# openSX70_MEROE_V7-1_20190603.net
KiCad netlist of a schematic drawn in EAGLE
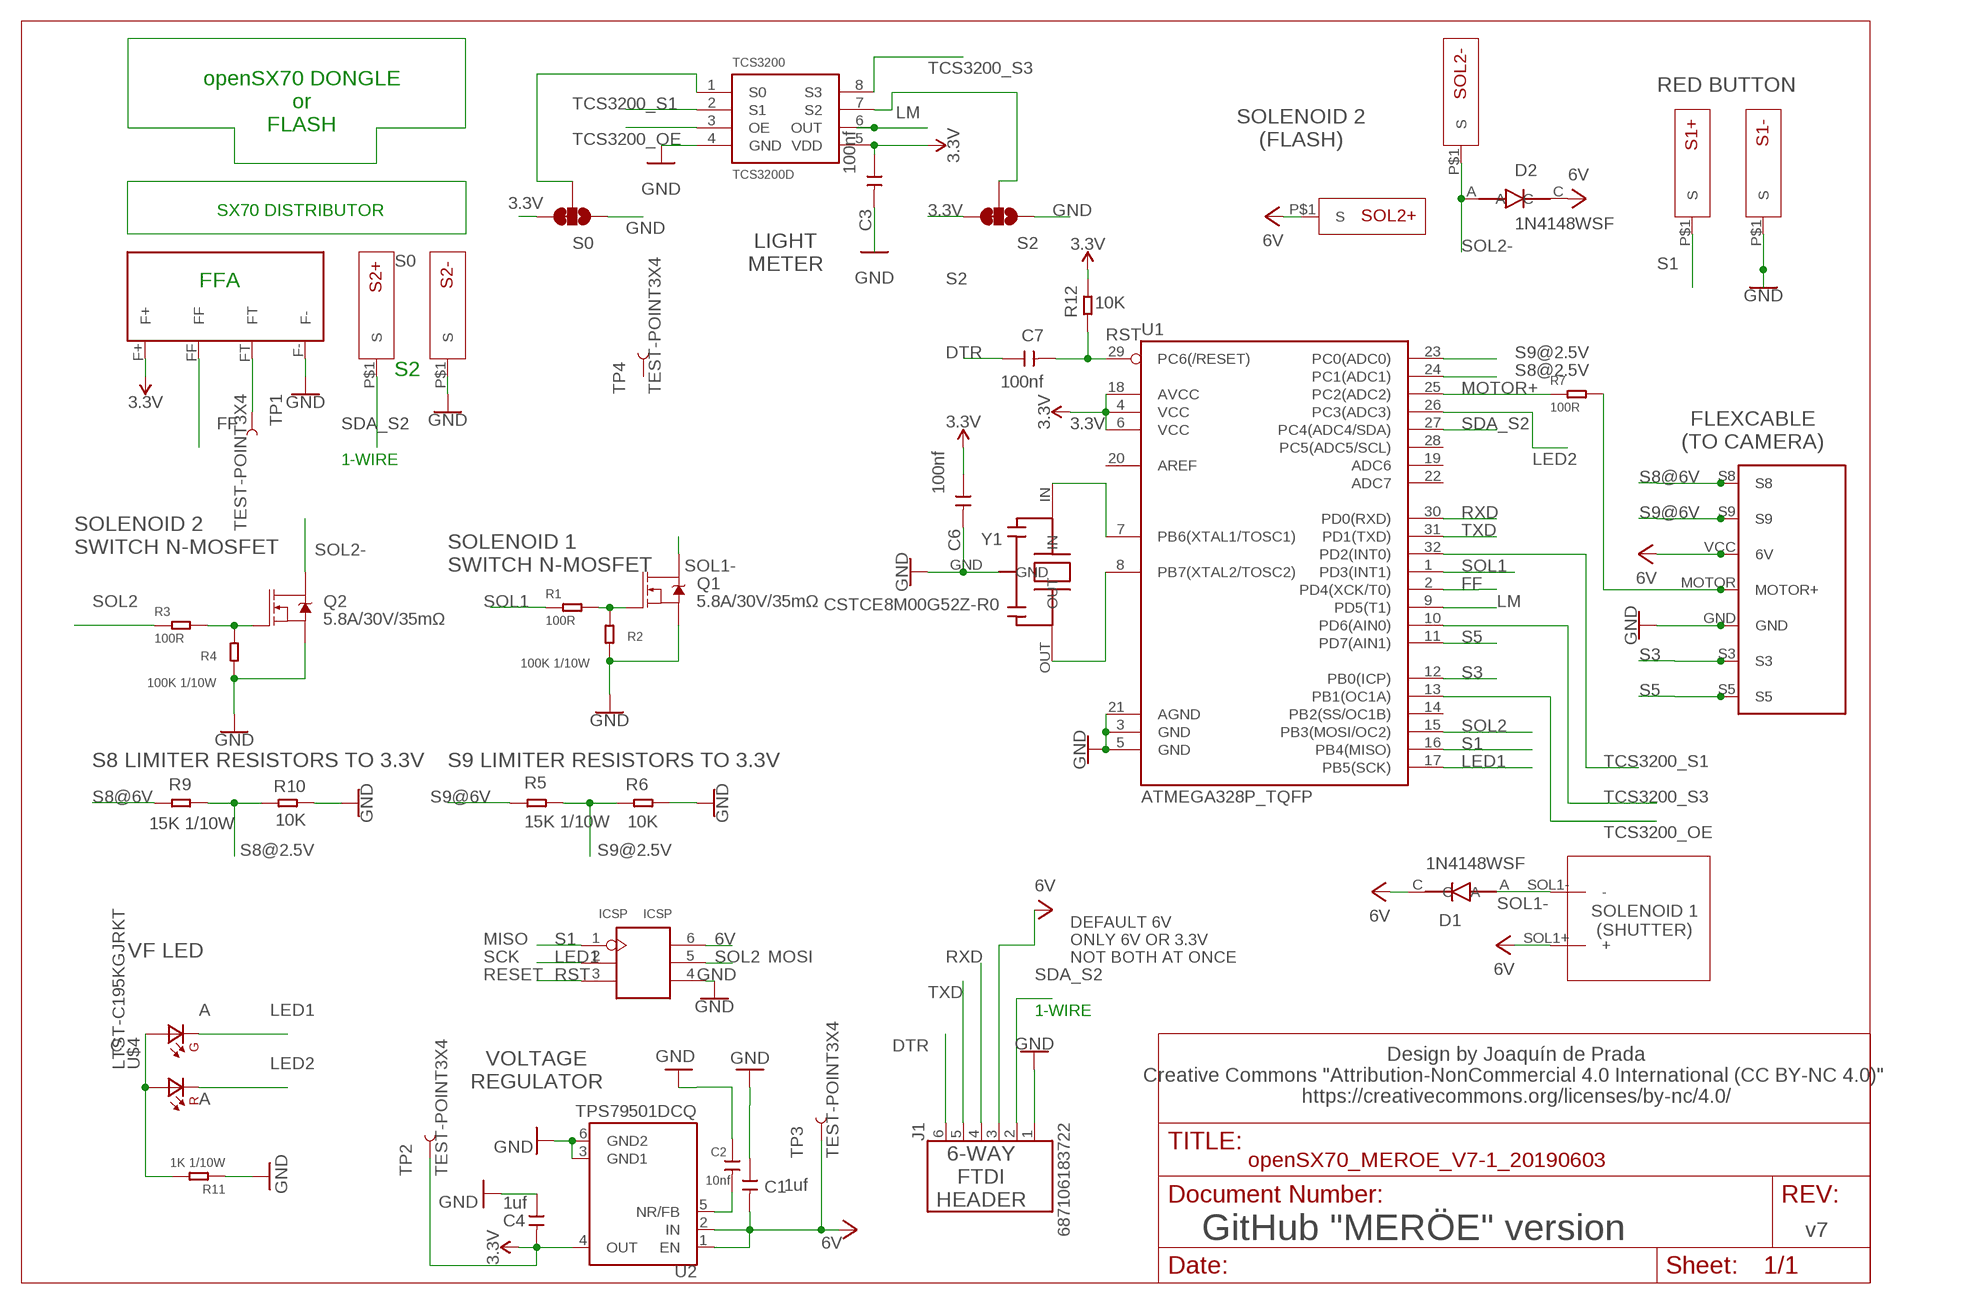
[diagram p0: schematic, sheet 1]

(export (version "E")
  (design (tool "Eeschema 10.0.6"))
  (components
    (comp (ref "C1")
      (value "1uf")
      (footprint "eagle-import:C0603")
      (fields (field (name "MPN") "CC0603KRX5R6BB106"))
      (libsource (lib "eagle-import") (part "CERAMIC-10UF-10V-10%-X5R(0603)"))
    )
    (comp (ref "C2")
      (value "10nf")
      (footprint "eagle-import:C0603")
      (fields (field (name "MPN") "CC0603KRX7R9BB104"))
      (libsource (lib "eagle-import") (part "CERAMIC-100NF-50V-10%-X7R(0603)"))
    )
    (comp (ref "C3")
      (value "100nf")
      (footprint "eagle-import:C0603")
      (fields (field (name "MPN") "CC0603KRX7R9BB104"))
      (libsource (lib "eagle-import") (part "CERAMIC-100NF-50V-10%-X7R(0603)"))
    )
    (comp (ref "C4")
      (value "1uf")
      (footprint "eagle-import:C0603")
      (fields (field (name "MPN") "CC0603KRX5R6BB106"))
      (libsource (lib "eagle-import") (part "CERAMIC-10UF-10V-10%-X5R(0603)"))
    )
    (comp (ref "C6")
      (value "100nf")
      (footprint "eagle-import:C0603")
      (fields (field (name "MPN") "CC0603KRX7R9BB104"))
      (libsource (lib "eagle-import") (part "CERAMIC-100NF-50V-10%-X7R(0603)"))
    )
    (comp (ref "C7")
      (value "100nf")
      (footprint "eagle-import:C0603")
      (fields (field (name "MPN") "CC0603KRX7R9BB104"))
      (libsource (lib "eagle-import") (part "CERAMIC-100NF-50V-10%-X7R(0603)"))
    )
    (comp (ref "D1")
      (value "1N4148WSF")
      (footprint "eagle-import:SODFL2512X100N")
      (fields (field (name "MANUFACTURER") "Fairchild Semiconductor"))
      (libsource (lib "eagle-import") (part "1N4148WS"))
    )
    (comp (ref "D2")
      (value "1N4148WSF")
      (footprint "eagle-import:SODFL2512X100N")
      (fields (field (name "MANUFACTURER") "Fairchild Semiconductor"))
      (libsource (lib "eagle-import") (part "1N4148WS"))
    )
    (comp (ref "ICSP")
      (value "ICSP")
      (footprint "eagle-import:H2X3-2.54")
      (libsource (lib "eagle-import") (part "ICSP"))
    )
    (comp (ref "J1")
      (value "687106183722")
      (footprint "eagle-import:687106183722")
      (fields (field (name "MF") "Wurth Electronics"))
      (libsource (lib "eagle-import") (part "687106183722"))
    )
    (comp (ref "Q1")
      (value "5.8A/30V/35mΩ")
      (footprint "eagle-import:SOT23-3")
      (libsource (lib "eagle-import") (part "MOSFET-NCH-AO3404A"))
    )
    (comp (ref "Q2")
      (value "5.8A/30V/35mΩ")
      (footprint "eagle-import:SOT23-3")
      (libsource (lib "eagle-import") (part "MOSFET-NCH-AO3404A"))
    )
    (comp (ref "R1")
      (value "100R")
      (footprint "eagle-import:R0603")
      (fields (field (name "MPN") "RC0603JR-07100RL"))
      (libsource (lib "eagle-import") (part "SMD-RES-100R-5%-1/10W(0603)"))
    )
    (comp (ref "R2")
      (value "100K 1/10W")
      (footprint "eagle-import:R0603")
      (fields (field (name "MPN") "RC0603JR-07100KL"))
      (libsource (lib "eagle-import") (part "SMD-RES-100K-5%-1/10W(0603)"))
    )
    (comp (ref "R3")
      (value "100R")
      (footprint "eagle-import:R0603")
      (fields (field (name "MPN") "RC0603JR-07100RL"))
      (libsource (lib "eagle-import") (part "SMD-RES-100R-5%-1/10W(0603)"))
    )
    (comp (ref "R4")
      (value "100K 1/10W")
      (footprint "eagle-import:R0603")
      (fields (field (name "MPN") "RC0603JR-07100KL"))
      (libsource (lib "eagle-import") (part "SMD-RES-100K-5%-1/10W(0603)"))
    )
    (comp (ref "R5")
      (value "15K 1/10W")
      (footprint "eagle-import:R0603")
      (fields (field (name "MPN") "RC0603FR-0715KL"))
      (libsource (lib "eagle-import") (part "SMD-RES-15K-1%-1/10W(0603)"))
    )
    (comp (ref "R6")
      (value "10K")
      (footprint "eagle-import:R0603")
      (fields (field (name "MPN") "RC0603FR-0710KL"))
      (libsource (lib "eagle-import") (part "SMD-RES-10K-1%-1/10W(0603)"))
    )
    (comp (ref "R7")
      (value "100R")
      (footprint "eagle-import:R0603")
      (fields (field (name "MPN") "RC0603JR-07100RL"))
      (libsource (lib "eagle-import") (part "SMD-RES-100R-5%-1/10W(0603)"))
    )
    (comp (ref "R9")
      (value "15K 1/10W")
      (footprint "eagle-import:R0603")
      (fields (field (name "MPN") "RC0603FR-0715KL"))
      (libsource (lib "eagle-import") (part "SMD-RES-15K-1%-1/10W(0603)"))
    )
    (comp (ref "R10")
      (value "10K")
      (footprint "eagle-import:R0603")
      (fields (field (name "MPN") "RC0603FR-0710KL"))
      (libsource (lib "eagle-import") (part "SMD-RES-10K-1%-1/10W(0603)"))
    )
    (comp (ref "R11")
      (value "1K 1/10W")
      (footprint "eagle-import:R0603")
      (fields (field (name "MPN") "RC0603JR-071KL"))
      (libsource (lib "eagle-import") (part "SMD-RES-1K-5%-1/10W(0603)"))
    )
    (comp (ref "R12")
      (value "10K")
      (footprint "eagle-import:R0603")
      (fields (field (name "MPN") "RC0603FR-0710KL"))
      (libsource (lib "eagle-import") (part "SMD-RES-10K-1%-1/10W(0603)"))
    )
    (comp (ref "S0")
      (value "S0")
      (footprint "eagle-import:SMT-JUMPER_3_1-NC_TRACE_SILK")
      (libsource (lib "eagle-import") (part "JUMPER-SMT_3_1-NC_TRACE_SILK"))
    )
    (comp (ref "S1+")
      (value "SX70-S-PAD-NEW")
      (footprint "eagle-import:SX70-S-PAD2")
      (libsource (lib "eagle-import") (part "SX70-S-PAD-NEW"))
    )
    (comp (ref "S1-")
      (value "SX70-S-PAD-NEW")
      (footprint "eagle-import:SX70-S-PAD2")
      (libsource (lib "eagle-import") (part "SX70-S-PAD-NEW"))
    )
    (comp (ref "S2")
      (value "S2")
      (footprint "eagle-import:SMT-JUMPER_3_1-NC_TRACE_SILK")
      (libsource (lib "eagle-import") (part "JUMPER-SMT_3_1-NC_TRACE_SILK"))
    )
    (comp (ref "S2+")
      (value "SX70-S-PAD-NEW")
      (footprint "eagle-import:SX70-S-PAD2")
      (libsource (lib "eagle-import") (part "SX70-S-PAD-NEW"))
    )
    (comp (ref "S2-")
      (value "SX70-S-PAD-NEW")
      (footprint "eagle-import:SX70-S-PAD2")
      (libsource (lib "eagle-import") (part "SX70-S-PAD-NEW"))
    )
    (comp (ref "SOL1")
      (value "SX70-SOLENOID1-2PADS")
      (footprint "eagle-import:SX70-SOLENOID1-2")
      (libsource (lib "eagle-import") (part "SX70-SOLENOID1-2PADS"))
    )
    (comp (ref "SOL2+")
      (value "SX70-S-PAD-NEW")
      (footprint "eagle-import:SX70-S-PAD2")
      (libsource (lib "eagle-import") (part "SX70-S-PAD-NEW"))
    )
    (comp (ref "SOL2-")
      (value "SX70-S-PAD-NEW")
      (footprint "eagle-import:SX70-S-PAD2")
      (libsource (lib "eagle-import") (part "SX70-S-PAD-NEW"))
    )
    (comp (ref "TCS3200")
      (value "TCS3200D")
      (footprint "eagle-import:SOIC8")
      (fields (field (name "MF") "ams") (field (name "MP") "TCS3200D-TR"))
      (libsource (lib "eagle-import") (part "TCS3200D"))
    )
    (comp (ref "TP1")
      (value "TEST-POINT3X4")
      (footprint "eagle-import:PAD.03X.04")
      (libsource (lib "eagle-import") (part "TEST-POINT3X4"))
    )
    (comp (ref "TP2")
      (value "TEST-POINT3X4")
      (footprint "eagle-import:PAD.03X.04")
      (libsource (lib "eagle-import") (part "TEST-POINT3X4"))
    )
    (comp (ref "TP3")
      (value "TEST-POINT3X4")
      (footprint "eagle-import:PAD.03X.04")
      (libsource (lib "eagle-import") (part "TEST-POINT3X4"))
    )
    (comp (ref "TP4")
      (value "TEST-POINT3X4")
      (footprint "eagle-import:PAD.03X.04")
      (libsource (lib "eagle-import") (part "TEST-POINT3X4"))
    )
    (comp (ref "U$1")
      (value "SX70-7-PAD")
      (footprint "eagle-import:SX70-7-PAD-PROPER")
      (libsource (lib "eagle-import") (part "SX70-7-PAD"))
    )
    (comp (ref "U$2")
      (value "FFA")
      (footprint "eagle-import:FFA-PAD-PACKAGE")
      (libsource (lib "eagle-import") (part "SX70-FFA-PAD"))
    )
    (comp (ref "U$4")
      (value "LTST-C195KGJRKT")
      (footprint "eagle-import:LTST-BILED-15X16")
      (fields (field (name "MF") "Lite-On Inc."))
      (libsource (lib "eagle-import") (part "LTST-C195KGJRKT"))
    )
    (comp (ref "U1")
      (value "ATMEGA328P_TQFP")
      (footprint "eagle-import:TQFP32-08")
      (libsource (lib "eagle-import") (part "ATMEGA328P_TQFP"))
    )
    (comp (ref "U2")
      (value "TPS79501DCQ")
      (footprint "eagle-import:SOT127P706X180-6N")
      (fields (field (name "MF") "Texas Instruments"))
      (libsource (lib "eagle-import") (part "TPS79501DCQ"))
    )
    (comp (ref "Y1")
      (value "CSTCE8M00G52Z-R0")
      (footprint "eagle-import:CFP95P160X100-3N")
      (fields (field (name "MF") "Murata") (field (name "MP") "CSTCE16M0V53-R0"))
      (libsource (lib "eagle-import") (part "CSTCE16M0V53-R0"))
    )
  )
  (nets
    (net (code "1") (name "/DTR") (class "Default")
      (node (ref "C7") (pin "1") (pinfunction "1_1") (pintype "passive"))
      (node (ref "J1") (pin "6") (pinfunction "1_6") (pintype "passive"))
    )
    (net (code "2") (name "/FF") (class "Default")
      (node (ref "U$2") (pin "FF") (pinfunction "FF_FF") (pintype "bidirectional"))
      (node (ref "U1") (pin "2") (pinfunction "PD4(XCK/T0)_2") (pintype "bidirectional"))
    )
    (net (code "3") (name "/LED1") (class "Default")
      (node (ref "ICSP") (pin "2") (pinfunction "SCK_2") (pintype "bidirectional"))
      (node (ref "U$4") (pin "P$3") (pinfunction "K1_P$3") (pintype "passive"))
      (node (ref "U1") (pin "17") (pinfunction "PB5(SCK)_17") (pintype "bidirectional"))
    )
    (net (code "4") (name "/LED2") (class "Default")
      (node (ref "U$4") (pin "P$4") (pinfunction "K2_P$4") (pintype "passive"))
      (node (ref "U1") (pin "26") (pinfunction "PC3(ADC3)_26") (pintype "bidirectional"))
    )
    (net (code "5") (name "/LM") (class "Default")
      (node (ref "TCS3200") (pin "6") (pinfunction "OUT_6") (pintype "bidirectional"))
      (node (ref "U1") (pin "9") (pinfunction "PD5(T1)_9") (pintype "bidirectional"))
    )
    (net (code "6") (name "/MOTOR+") (class "Default")
      (node (ref "R7") (pin "1") (pinfunction "1_1") (pintype "passive"))
      (node (ref "U1") (pin "25") (pinfunction "PC2(ADC2)_25") (pintype "bidirectional"))
    )
    (net (code "7") (name "/RST") (class "Default")
      (node (ref "C7") (pin "2") (pinfunction "2_2") (pintype "passive"))
      (node (ref "ICSP") (pin "3") (pinfunction "RST_3") (pintype "bidirectional"))
      (node (ref "R12") (pin "1") (pinfunction "1_1") (pintype "passive"))
      (node (ref "U1") (pin "29") (pinfunction "PC6(/RESET)_29") (pintype "bidirectional"))
    )
    (net (code "8") (name "/RXD") (class "Default")
      (node (ref "J1") (pin "4") (pinfunction "3_4") (pintype "passive"))
      (node (ref "U1") (pin "30") (pinfunction "PD0(RXD)_30") (pintype "bidirectional"))
    )
    (net (code "9") (name "/S1") (class "Default")
      (node (ref "ICSP") (pin "1") (pinfunction "MISO_1") (pintype "bidirectional"))
      (node (ref "S1+") (pin "P$1") (pinfunction "S_P$1") (pintype "bidirectional"))
      (node (ref "U1") (pin "16") (pinfunction "PB4(MISO)_16") (pintype "bidirectional"))
    )
    (net (code "10") (name "/S3") (class "Default")
      (node (ref "U$1") (pin "S3") (pinfunction "S3_S3") (pintype "bidirectional"))
      (node (ref "U1") (pin "12") (pinfunction "PB0(ICP)_12") (pintype "bidirectional"))
    )
    (net (code "11") (name "/S5") (class "Default")
      (node (ref "U$1") (pin "S5") (pinfunction "S5_S5") (pintype "bidirectional"))
      (node (ref "U1") (pin "11") (pinfunction "PD7(AIN1)_11") (pintype "bidirectional"))
    )
    (net (code "12") (name "/S8@2.5V") (class "Default")
      (node (ref "R10") (pin "1") (pinfunction "1_1") (pintype "passive"))
      (node (ref "R9") (pin "2") (pinfunction "2_2") (pintype "passive"))
      (node (ref "U1") (pin "24") (pinfunction "PC1(ADC1)_24") (pintype "bidirectional"))
    )
    (net (code "13") (name "/S8@6V") (class "Default")
      (node (ref "R9") (pin "1") (pinfunction "1_1") (pintype "passive"))
      (node (ref "U$1") (pin "S8") (pinfunction "S8_S8") (pintype "bidirectional"))
    )
    (net (code "14") (name "/S9@2.5V") (class "Default")
      (node (ref "R5") (pin "2") (pinfunction "2_2") (pintype "passive"))
      (node (ref "R6") (pin "1") (pinfunction "1_1") (pintype "passive"))
      (node (ref "U1") (pin "23") (pinfunction "PC0(ADC0)_23") (pintype "bidirectional"))
    )
    (net (code "15") (name "/S9@6V") (class "Default")
      (node (ref "R5") (pin "1") (pinfunction "1_1") (pintype "passive"))
      (node (ref "U$1") (pin "S9") (pinfunction "S9_S9") (pintype "bidirectional"))
    )
    (net (code "16") (name "/SDA_S2") (class "Default")
      (node (ref "J1") (pin "2") (pinfunction "5_2") (pintype "passive"))
      (node (ref "S2+") (pin "P$1") (pinfunction "S_P$1") (pintype "bidirectional"))
      (node (ref "U1") (pin "27") (pinfunction "PC4(ADC4/SDA)_27") (pintype "bidirectional"))
    )
    (net (code "17") (name "/SOL1") (class "Default")
      (node (ref "R1") (pin "1") (pinfunction "1_1") (pintype "passive"))
      (node (ref "U1") (pin "1") (pinfunction "PD3(INT1)_1") (pintype "bidirectional"))
    )
    (net (code "18") (name "/SOL1-") (class "Default")
      (node (ref "D1") (pin "A") (pinfunction "A_A") (pintype "passive"))
      (node (ref "Q1") (pin "3") (pinfunction "D_3") (pintype "bidirectional"))
      (node (ref "SOL1") (pin "SOL1-") (pinfunction "-_SOL1-") (pintype "bidirectional"))
    )
    (net (code "19") (name "/SOL2") (class "Default")
      (node (ref "ICSP") (pin "5") (pinfunction "MOSI_5") (pintype "bidirectional"))
      (node (ref "R3") (pin "1") (pinfunction "1_1") (pintype "passive"))
      (node (ref "U1") (pin "15") (pinfunction "PB3(MOSI/OC2)_15") (pintype "bidirectional"))
    )
    (net (code "20") (name "/SOL2-") (class "Default")
      (node (ref "D2") (pin "A") (pinfunction "A_A") (pintype "passive"))
      (node (ref "Q2") (pin "3") (pinfunction "D_3") (pintype "bidirectional"))
      (node (ref "SOL2-") (pin "P$1") (pinfunction "S_P$1") (pintype "bidirectional"))
    )
    (net (code "21") (name "/TCS3200_OE") (class "Default")
      (node (ref "TCS3200") (pin "3") (pinfunction "OE_3") (pintype "bidirectional"))
      (node (ref "U1") (pin "13") (pinfunction "PB1(OC1A)_13") (pintype "bidirectional"))
    )
    (net (code "22") (name "/TCS3200_S1") (class "Default")
      (node (ref "TCS3200") (pin "2") (pinfunction "S1_2") (pintype "bidirectional"))
      (node (ref "U1") (pin "32") (pinfunction "PD2(INT0)_32") (pintype "bidirectional"))
    )
    (net (code "23") (name "/TCS3200_S3") (class "Default")
      (node (ref "TCS3200") (pin "8") (pinfunction "S3_8") (pintype "bidirectional"))
      (node (ref "U1") (pin "10") (pinfunction "PD6(AIN0)_10") (pintype "bidirectional"))
    )
    (net (code "24") (name "/TXD") (class "Default")
      (node (ref "J1") (pin "5") (pinfunction "2_5") (pintype "passive"))
      (node (ref "U1") (pin "31") (pinfunction "PD1(TXD)_31") (pintype "bidirectional"))
    )
    (net (code "25") (name "3.3V") (class "Default")
      (node (ref "C3") (pin "1") (pinfunction "1_1") (pintype "passive"))
      (node (ref "C4") (pin "2") (pinfunction "2_2") (pintype "passive"))
      (node (ref "C6") (pin "1") (pinfunction "1_1") (pintype "passive"))
      (node (ref "R12") (pin "2") (pinfunction "2_2") (pintype "passive"))
      (node (ref "S0") (pin "3") (pinfunction "3_3") (pintype "passive"))
      (node (ref "S2") (pin "3") (pinfunction "3_3") (pintype "passive"))
      (node (ref "TCS3200") (pin "5") (pinfunction "VDD_5") (pintype "bidirectional"))
      (node (ref "TP2") (pin "P$1") (pinfunction "1_P$1") (pintype "bidirectional"))
      (node (ref "U$2") (pin "F+") (pinfunction "F+_F+") (pintype "bidirectional"))
      (node (ref "U1") (pin "18") (pinfunction "AVCC_18") (pintype "bidirectional"))
      (node (ref "U1") (pin "4") (pinfunction "VCC_4") (pintype "bidirectional"))
      (node (ref "U1") (pin "6") (pinfunction "VCC_6") (pintype "bidirectional"))
      (node (ref "U2") (pin "4") (pinfunction "OUT_4") (pintype "output"))
    )
    (net (code "26") (name "6V") (class "Default")
      (node (ref "C1") (pin "2") (pinfunction "2_2") (pintype "passive"))
      (node (ref "D1") (pin "C") (pinfunction "C_C") (pintype "passive"))
      (node (ref "D2") (pin "C") (pinfunction "C_C") (pintype "passive"))
      (node (ref "ICSP") (pin "6") (pinfunction "VCC_6") (pintype "bidirectional"))
      (node (ref "J1") (pin "3") (pinfunction "4_3") (pintype "passive"))
      (node (ref "SOL1") (pin "SOL1+") (pinfunction "+_SOL1+") (pintype "bidirectional"))
      (node (ref "SOL2+") (pin "P$1") (pinfunction "S_P$1") (pintype "bidirectional"))
      (node (ref "TP3") (pin "P$1") (pinfunction "1_P$1") (pintype "bidirectional"))
      (node (ref "U$1") (pin "VCC") (pinfunction "6V_VCC") (pintype "bidirectional"))
      (node (ref "U2") (pin "1") (pinfunction "EN_1") (pintype "input"))
      (node (ref "U2") (pin "2") (pinfunction "IN_2") (pintype "input"))
    )
    (net (code "27") (name "GND") (class "Default")
      (node (ref "C1") (pin "1") (pinfunction "1_1") (pintype "passive"))
      (node (ref "C2") (pin "1") (pinfunction "1_1") (pintype "passive"))
      (node (ref "C3") (pin "2") (pinfunction "2_2") (pintype "passive"))
      (node (ref "C4") (pin "1") (pinfunction "1_1") (pintype "passive"))
      (node (ref "C6") (pin "2") (pinfunction "2_2") (pintype "passive"))
      (node (ref "ICSP") (pin "4") (pinfunction "GND_4") (pintype "bidirectional"))
      (node (ref "J1") (pin "1") (pinfunction "6_1") (pintype "passive"))
      (node (ref "Q1") (pin "2") (pinfunction "S_2") (pintype "bidirectional"))
      (node (ref "Q2") (pin "2") (pinfunction "S_2") (pintype "bidirectional"))
      (node (ref "R10") (pin "2") (pinfunction "2_2") (pintype "passive"))
      (node (ref "R11") (pin "1") (pinfunction "1_1") (pintype "passive"))
      (node (ref "R2") (pin "1") (pinfunction "1_1") (pintype "passive"))
      (node (ref "R4") (pin "1") (pinfunction "1_1") (pintype "passive"))
      (node (ref "R6") (pin "2") (pinfunction "2_2") (pintype "passive"))
      (node (ref "S0") (pin "1") (pinfunction "1_1") (pintype "passive"))
      (node (ref "S1-") (pin "P$1") (pinfunction "S_P$1") (pintype "bidirectional"))
      (node (ref "S2") (pin "1") (pinfunction "1_1") (pintype "passive"))
      (node (ref "S2-") (pin "P$1") (pinfunction "S_P$1") (pintype "bidirectional"))
      (node (ref "TCS3200") (pin "4") (pinfunction "GND_4") (pintype "bidirectional"))
      (node (ref "U$1") (pin "GND") (pinfunction "GND_GND") (pintype "bidirectional"))
      (node (ref "U$2") (pin "F-") (pinfunction "F-_F-") (pintype "bidirectional"))
      (node (ref "U1") (pin "21") (pinfunction "AGND_21") (pintype "bidirectional"))
      (node (ref "U1") (pin "3") (pinfunction "GND_3") (pintype "bidirectional"))
      (node (ref "U1") (pin "5") (pinfunction "GND_5") (pintype "bidirectional"))
      (node (ref "U2") (pin "3") (pinfunction "GND1_3") (pintype "power_in"))
      (node (ref "U2") (pin "6") (pinfunction "GND2_6") (pintype "power_in"))
      (node (ref "Y1") (pin "GND") (pinfunction "GND_GND") (pintype "passive"))
    )
    (net (code "28") (name "Net-(Q1-G)") (class "Default")
      (node (ref "Q1") (pin "1") (pinfunction "G_1") (pintype "bidirectional"))
      (node (ref "R1") (pin "2") (pinfunction "2_2") (pintype "passive"))
      (node (ref "R2") (pin "2") (pinfunction "2_2") (pintype "passive"))
    )
    (net (code "29") (name "Net-(Q2-G)") (class "Default")
      (node (ref "Q2") (pin "1") (pinfunction "G_1") (pintype "bidirectional"))
      (node (ref "R3") (pin "2") (pinfunction "2_2") (pintype "passive"))
      (node (ref "R4") (pin "2") (pinfunction "2_2") (pintype "passive"))
    )
    (net (code "30") (name "Net-(TCS3200-S0)") (class "Default")
      (node (ref "S0") (pin "2") (pinfunction "2_2") (pintype "passive"))
      (node (ref "TCS3200") (pin "1") (pinfunction "S0_1") (pintype "bidirectional"))
    )
    (net (code "31") (name "Net-(TCS3200-S2)") (class "Default")
      (node (ref "S2") (pin "2") (pinfunction "2_2") (pintype "passive"))
      (node (ref "TCS3200") (pin "7") (pinfunction "S2_7") (pintype "bidirectional"))
    )
    (net (code "32") (name "Net-(TP1-1)") (class "Default")
      (node (ref "TP1") (pin "P$1") (pinfunction "1_P$1") (pintype "bidirectional"))
      (node (ref "U$2") (pin "FT") (pinfunction "FT_FT") (pintype "bidirectional"))
    )
    (net (code "33") (name "Net-(U$1-MOTOR+)") (class "Default")
      (node (ref "R7") (pin "2") (pinfunction "2_2") (pintype "passive"))
      (node (ref "U$1") (pin "MOTOR") (pinfunction "MOTOR+_MOTOR") (pintype "bidirectional"))
    )
    (net (code "34") (name "Net-(U$4-A1)") (class "Default")
      (node (ref "R11") (pin "2") (pinfunction "2_2") (pintype "passive"))
      (node (ref "U$4") (pin "P$1") (pinfunction "A1_P$1") (pintype "passive"))
      (node (ref "U$4") (pin "P$2") (pinfunction "A2_P$2") (pintype "passive"))
    )
    (net (code "35") (name "Net-(U1-PB6(XTAL1{slash}TOSC1))") (class "Default")
      (node (ref "U1") (pin "7") (pinfunction "PB6(XTAL1/TOSC1)_7") (pintype "bidirectional"))
      (node (ref "Y1") (pin "IN") (pinfunction "IN_IN") (pintype "input"))
    )
    (net (code "36") (name "Net-(U1-PB7(XTAL2{slash}TOSC2))") (class "Default")
      (node (ref "U1") (pin "8") (pinfunction "PB7(XTAL2/TOSC2)_8") (pintype "bidirectional"))
      (node (ref "Y1") (pin "OUT") (pinfunction "OUT_OUT") (pintype "output"))
    )
    (net (code "37") (name "Net-(U2-NR{slash}FB)") (class "Default")
      (node (ref "C2") (pin "2") (pinfunction "2_2") (pintype "passive"))
      (node (ref "U2") (pin "5") (pinfunction "NR/FB_5") (pintype "input"))
    )
    (net (code "38") (name "unconnected-(TP4-1-PadP$1)") (class "Default")
      (node (ref "TP4") (pin "P$1") (pinfunction "1_P$1") (pintype "bidirectional"))
    )
    (net (code "39") (name "unconnected-(U1-ADC6-Pad19)") (class "Default")
      (node (ref "U1") (pin "19") (pinfunction "ADC6_19") (pintype "bidirectional"))
    )
    (net (code "40") (name "unconnected-(U1-ADC7-Pad22)") (class "Default")
      (node (ref "U1") (pin "22") (pinfunction "ADC7_22") (pintype "bidirectional"))
    )
    (net (code "41") (name "unconnected-(U1-AREF-Pad20)") (class "Default")
      (node (ref "U1") (pin "20") (pinfunction "AREF_20") (pintype "bidirectional"))
    )
    (net (code "42") (name "unconnected-(U1-PB2(SS{slash}OC1B)-Pad14)") (class "Default")
      (node (ref "U1") (pin "14") (pinfunction "PB2(SS/OC1B)_14") (pintype "bidirectional"))
    )
    (net (code "43") (name "unconnected-(U1-PC5(ADC5{slash}SCL)-Pad28)") (class "Default")
      (node (ref "U1") (pin "28") (pinfunction "PC5(ADC5/SCL)_28") (pintype "bidirectional"))
    )
  )
)
